# 19_WIFI_BLE.net
KiCad netlist of a schematic drawn in Altium Designer
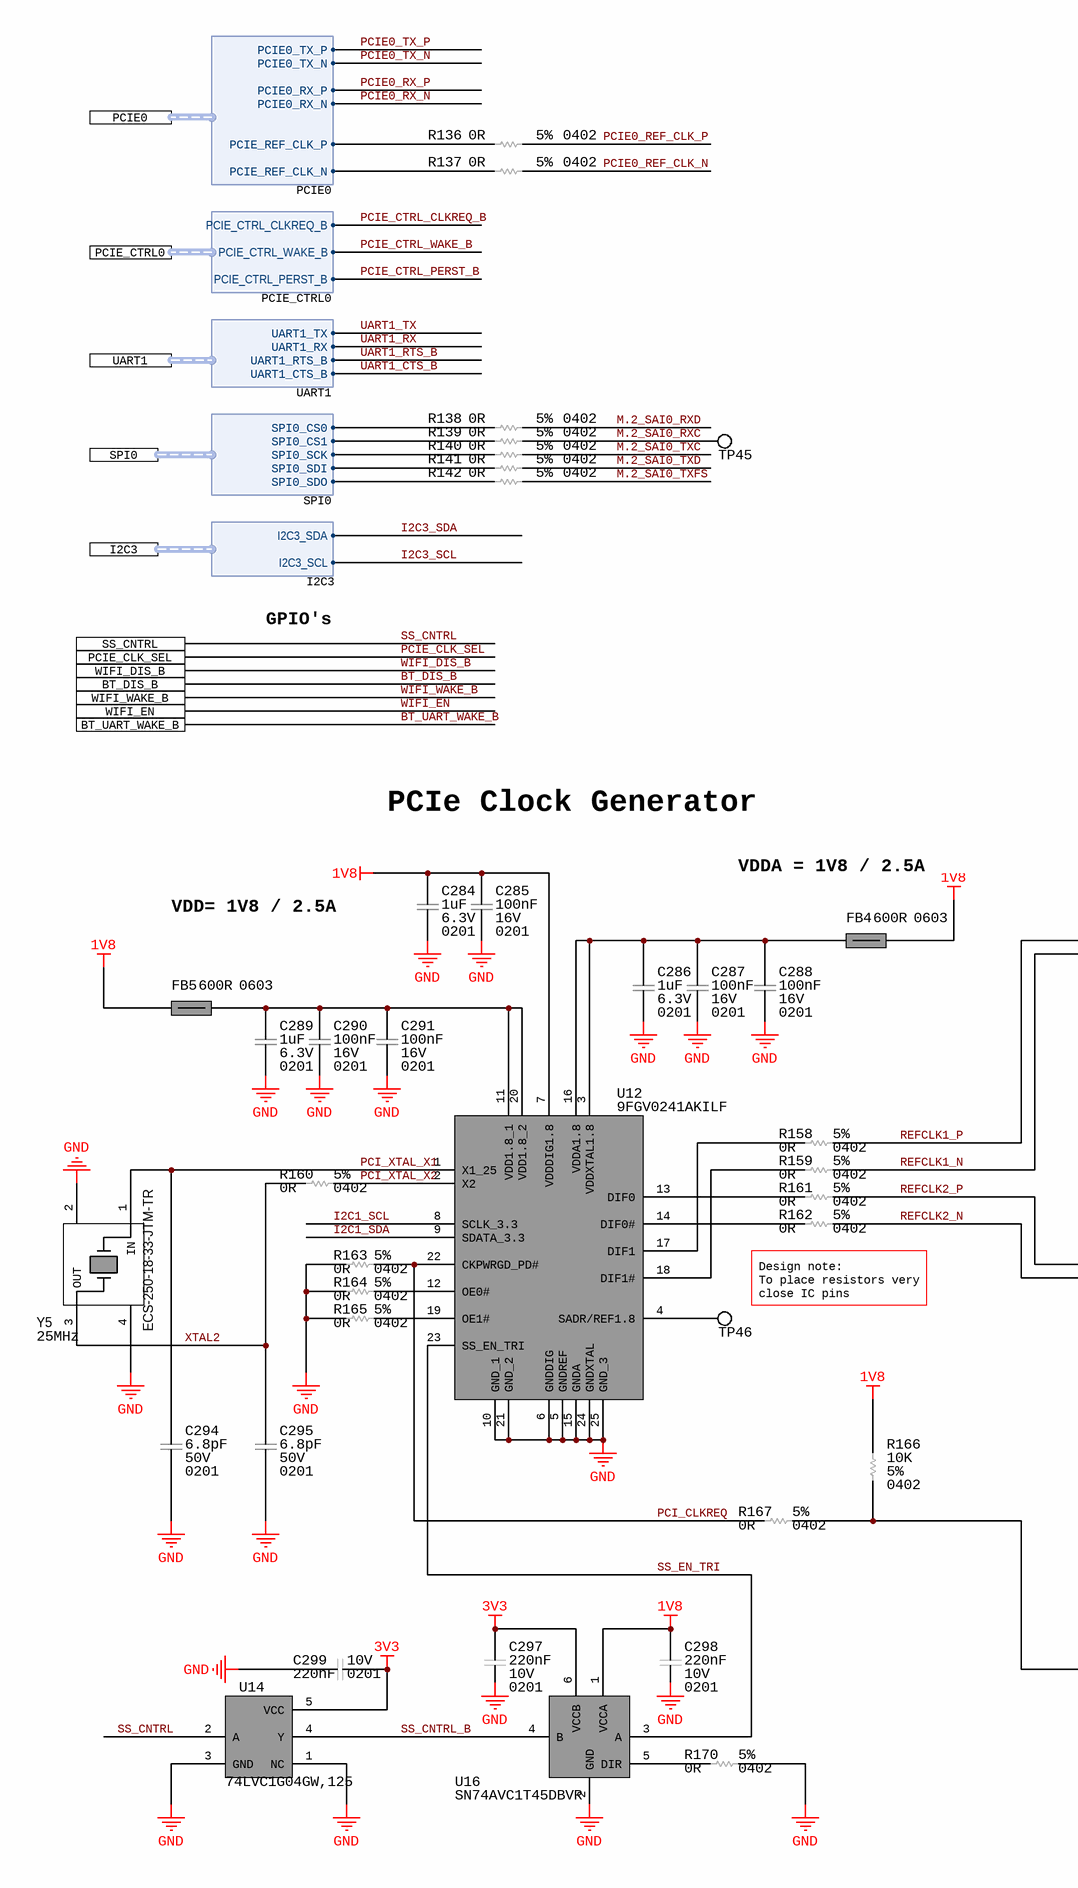
[diagram p0: 19_WIFI_BLE.SchDoc, left]
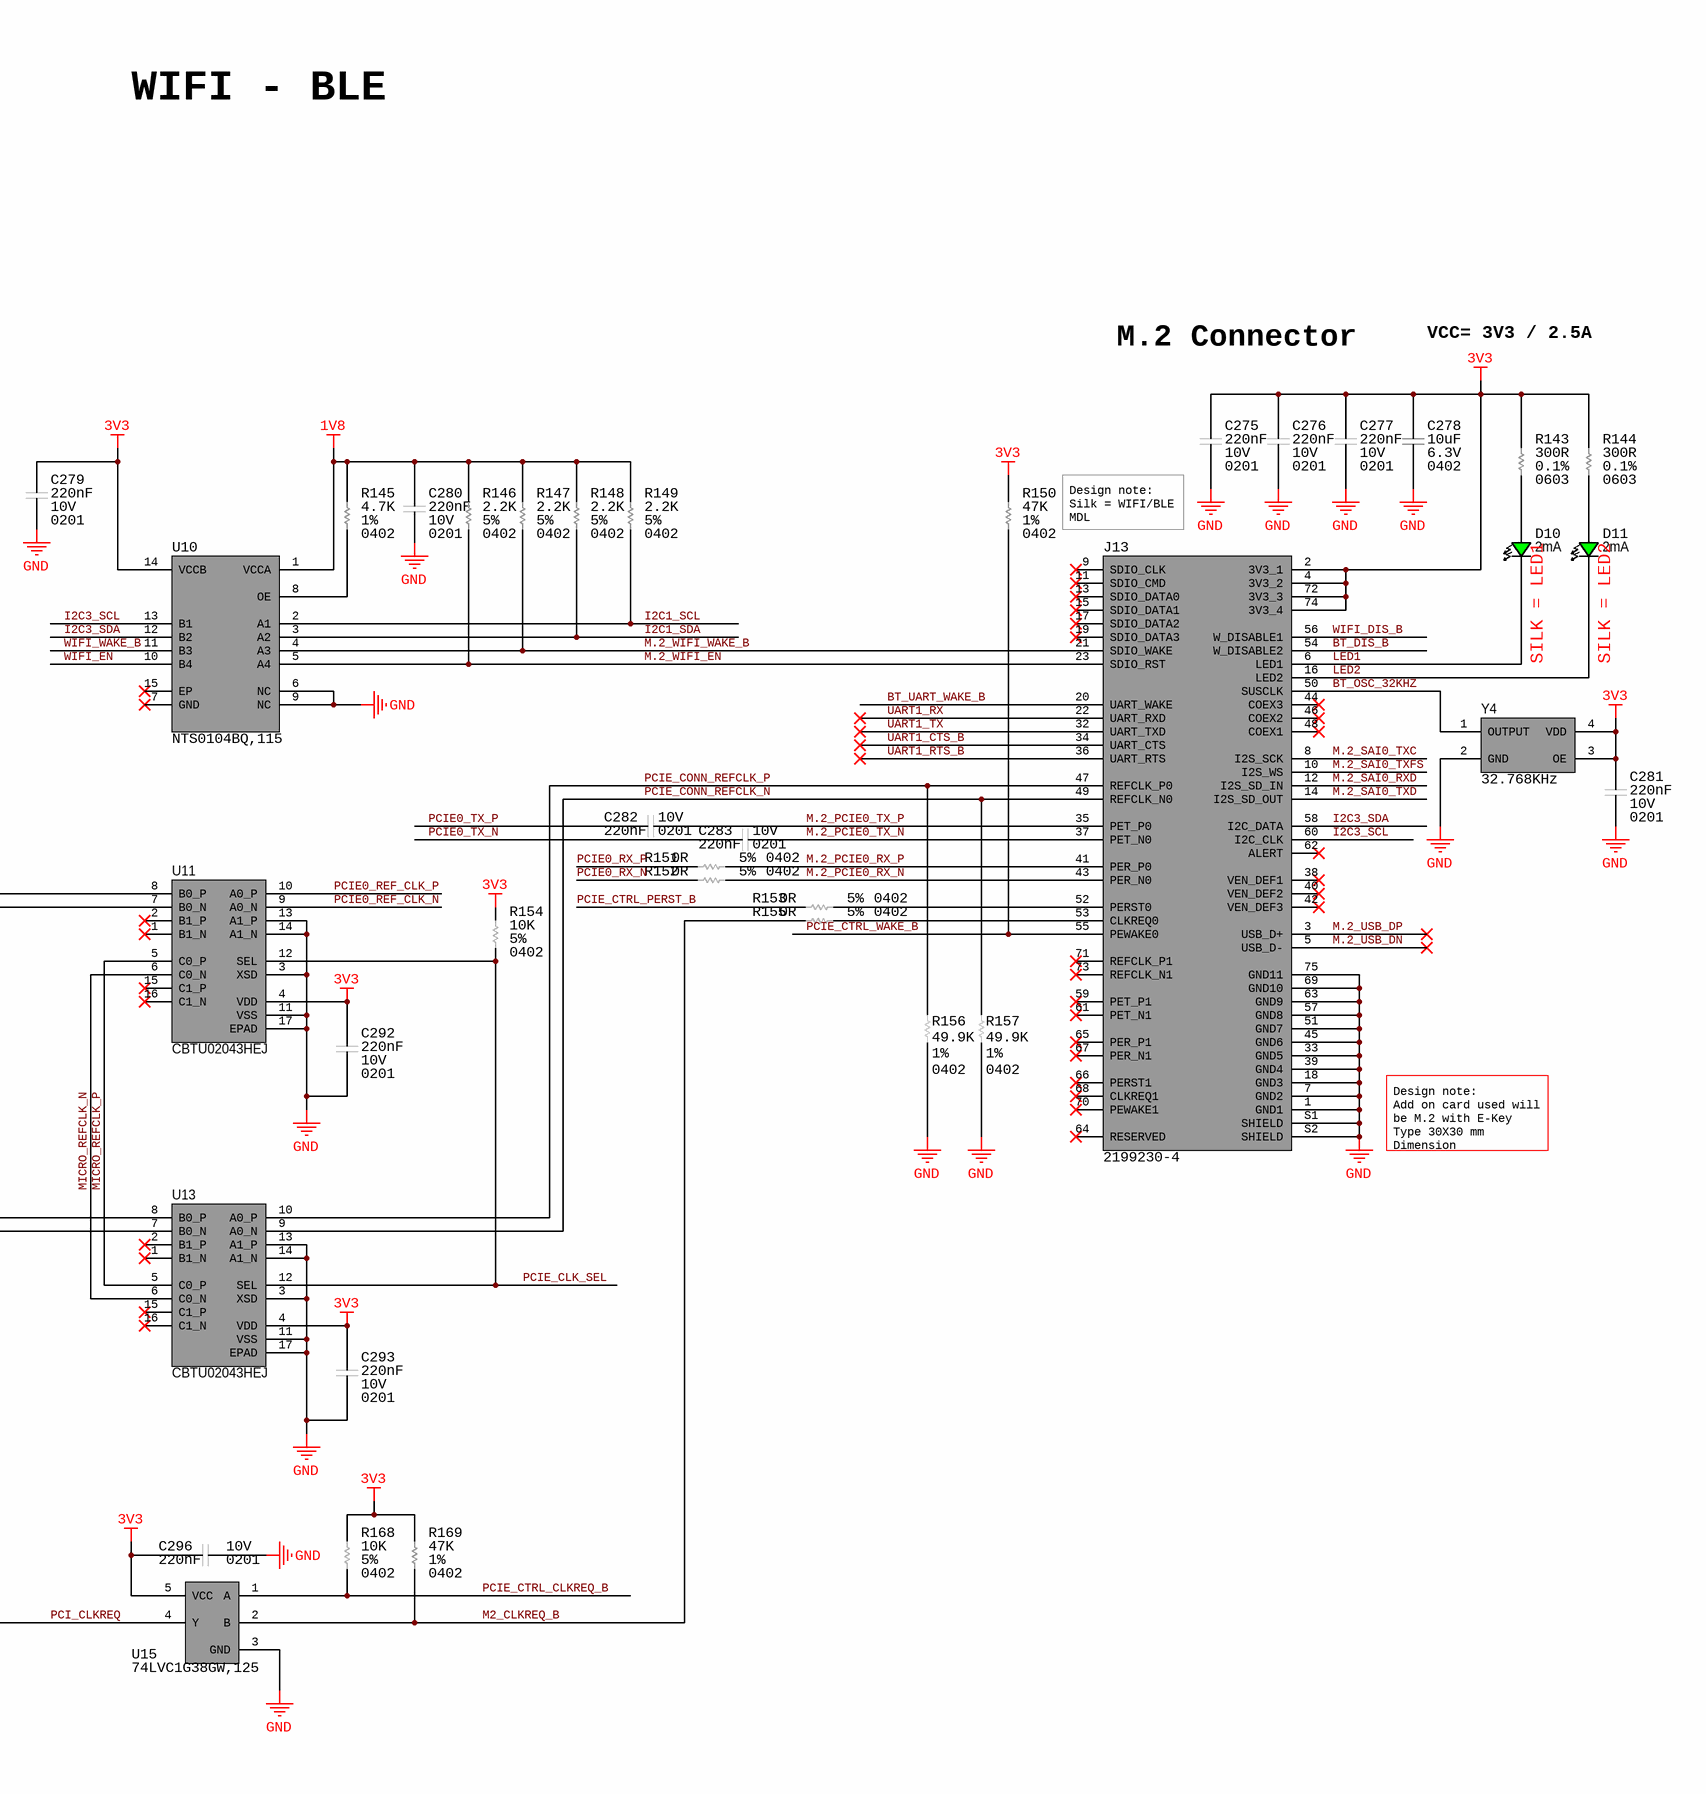
[diagram p1: 19_WIFI_BLE.SchDoc, right]

(export (version "E")
  (design (tool "Eeschema 10.0.6"))
  (components
    (comp (ref "C275")
      (value "LMK063BJ224MP-F")
      (footprint "CAP_0201_CAPC0603X03N")
      (description "Multilayer Ceramic Capacitors (High dielectric type), 10V, 0.22 uF, ± 20 %, 0201, X5R, RoHS")
      (fields
        (field (name "MANUFACTURER") "Taiyo Yuden")
        (field (name "TOLERANCE") "20%")
        (field (name "VOLTAGE RATING (DC)") "10V")
        (field (name "CAPACITANCE") "220nF")
        (field (name "CASE/PACKAGE") "0201")
      )
      (libsource (lib "Electronic Devices_LIB") (part "CAP_0.22UF_10V_X5R_0201"))
    )
    (comp (ref "C276")
      (value "LMK063BJ224MP-F")
      (footprint "CAP_0201_CAPC0603X03N")
      (description "Multilayer Ceramic Capacitors (High dielectric type), 10V, 0.22 uF, ± 20 %, 0201, X5R, RoHS")
      (fields
        (field (name "MANUFACTURER") "Taiyo Yuden")
        (field (name "TOLERANCE") "20%")
        (field (name "VOLTAGE RATING (DC)") "10V")
        (field (name "CAPACITANCE") "220nF")
        (field (name "CASE/PACKAGE") "0201")
      )
      (libsource (lib "Electronic Devices_LIB") (part "CAP_0.22UF_10V_X5R_0201"))
    )
    (comp (ref "C277")
      (value "LMK063BJ224MP-F")
      (footprint "CAP_0201_CAPC0603X03N")
      (description "Multilayer Ceramic Capacitors (High dielectric type), 10V, 0.22 uF, ± 20 %, 0201, X5R, RoHS")
      (fields
        (field (name "MANUFACTURER") "Taiyo Yuden")
        (field (name "TOLERANCE") "20%")
        (field (name "VOLTAGE RATING (DC)") "10V")
        (field (name "CAPACITANCE") "220nF")
        (field (name "CASE/PACKAGE") "0201")
      )
      (libsource (lib "Electronic Devices_LIB") (part "CAP_0.22UF_10V_X5R_0201"))
    )
    (comp (ref "C278")
      (value "CL05A106MQ5NUNC")
      (footprint "CAP_0402_CAPC1005X05N")
      (description "Cap Ceramic 10uF 6.3V X5R 20% SMD 0402 85C T/R")
      (fields
        (field (name "MANUFACTURER") "Samsung")
        (field (name "TOLERANCE") "20%")
        (field (name "CASE/PACKAGE") "0402")
        (field (name "CAPACITANCE") "10uF")
        (field (name "VOLTAGE RATING") "6.3V")
      )
      (libsource (lib "Electronic Devices_LIB") (part "CAP_10UF_6.3V_X5R_0402"))
    )
    (comp (ref "C279")
      (value "LMK063BJ224MP-F")
      (footprint "CAP_0201_CAPC0603X03N")
      (description "Multilayer Ceramic Capacitors (High dielectric type), 10V, 0.22 uF, ± 20 %, 0201, X5R, RoHS")
      (fields
        (field (name "MANUFACTURER") "Taiyo Yuden")
        (field (name "TOLERANCE") "20%")
        (field (name "VOLTAGE RATING (DC)") "10V")
        (field (name "CAPACITANCE") "220nF")
        (field (name "CASE/PACKAGE") "0201")
      )
      (libsource (lib "Electronic Devices_LIB") (part "CAP_0.22UF_10V_X5R_0201"))
    )
    (comp (ref "C280")
      (value "LMK063BJ224MP-F")
      (footprint "CAP_0201_CAPC0603X03N")
      (description "Multilayer Ceramic Capacitors (High dielectric type), 10V, 0.22 uF, ± 20 %, 0201, X5R, RoHS")
      (fields
        (field (name "MANUFACTURER") "Taiyo Yuden")
        (field (name "TOLERANCE") "20%")
        (field (name "VOLTAGE RATING (DC)") "10V")
        (field (name "CAPACITANCE") "220nF")
        (field (name "CASE/PACKAGE") "0201")
      )
      (libsource (lib "Electronic Devices_LIB") (part "CAP_0.22UF_10V_X5R_0201"))
    )
    (comp (ref "C281")
      (value "LMK063BJ224MP-F")
      (footprint "CAP_0201_CAPC0603X03N")
      (description "Multilayer Ceramic Capacitors (High dielectric type), 10V, 0.22 uF, ± 20 %, 0201, X5R, RoHS")
      (fields
        (field (name "MANUFACTURER") "Taiyo Yuden")
        (field (name "TOLERANCE") "20%")
        (field (name "VOLTAGE RATING (DC)") "10V")
        (field (name "CAPACITANCE") "220nF")
        (field (name "CASE/PACKAGE") "0201")
      )
      (libsource (lib "Electronic Devices_LIB") (part "CAP_0.22UF_10V_X5R_0201"))
    )
    (comp (ref "C282")
      (value "LMK063BJ224MP-F")
      (footprint "CAP_0201_CAPC0603X03N")
      (description "Multilayer Ceramic Capacitors (High dielectric type), 10V, 0.22 uF, ± 20 %, 0201, X5R, RoHS")
      (fields
        (field (name "MANUFACTURER") "Taiyo Yuden")
        (field (name "TOLERANCE") "20%")
        (field (name "VOLTAGE RATING (DC)") "10V")
        (field (name "CAPACITANCE") "220nF")
        (field (name "CASE/PACKAGE") "0201")
      )
      (libsource (lib "Electronic Devices_LIB") (part "CAP_0.22UF_10V_X5R_0201"))
    )
    (comp (ref "C283")
      (value "LMK063BJ224MP-F")
      (footprint "CAP_0201_CAPC0603X03N")
      (description "Multilayer Ceramic Capacitors (High dielectric type), 10V, 0.22 uF, ± 20 %, 0201, X5R, RoHS")
      (fields
        (field (name "MANUFACTURER") "Taiyo Yuden")
        (field (name "TOLERANCE") "20%")
        (field (name "VOLTAGE RATING (DC)") "10V")
        (field (name "CAPACITANCE") "220nF")
        (field (name "CASE/PACKAGE") "0201")
      )
      (libsource (lib "Electronic Devices_LIB") (part "CAP_0.22UF_10V_X5R_0201"))
    )
    (comp (ref "C284")
      (value "02016D105MAT2A")
      (footprint "CAP_0201_CAPC0603X03N")
      (description "0201 1 uF 6.3 V ±20 % Tolerance X5R Surface Mount Multilayer Ceramic Capacitor")
      (fields
        (field (name "MANUFACTURER") "Kyocera AVX")
        (field (name "TOLERANCE") "20%")
        (field (name "VOLTAGE RATING (DC)") "6.3V")
        (field (name "CAPACITANCE") "1uF")
        (field (name "CASE/PACKAGE") "0201")
      )
      (libsource (lib "Electronic Devices_LIB") (part "CAP_1UF_6.3V_X5R_0201"))
    )
    (comp (ref "C285")
      (value "GRM033C71C104KE14D")
      (footprint "CAP_0201_CAPC0603X03N")
      (description "Multilayer Ceramic Capacitor, 0.1 uF, 16 V, ± 10%, X7S, 0201 [0603 Metric]")
      (fields
        (field (name "MANUFACTURER") "Murata")
        (field (name "TOLERANCE") "10%")
        (field (name "VOLTAGE RATING") "16V")
        (field (name "CAPACITANCE") "100nF")
        (field (name "CASE/PACKAGE") "0201")
      )
      (libsource (lib "Electronic Devices_LIB") (part "CAP_100nF_16V_X7S_0201"))
    )
    (comp (ref "C286")
      (value "02016D105MAT2A")
      (footprint "CAP_0201_CAPC0603X03N")
      (description "0201 1 uF 6.3 V ±20 % Tolerance X5R Surface Mount Multilayer Ceramic Capacitor")
      (fields
        (field (name "MANUFACTURER") "Kyocera AVX")
        (field (name "TOLERANCE") "20%")
        (field (name "VOLTAGE RATING (DC)") "6.3V")
        (field (name "CAPACITANCE") "1uF")
        (field (name "CASE/PACKAGE") "0201")
      )
      (libsource (lib "Electronic Devices_LIB") (part "CAP_1UF_6.3V_X5R_0201"))
    )
    (comp (ref "C287")
      (value "GRM033C71C104KE14D")
      (footprint "CAP_0201_CAPC0603X03N")
      (description "Multilayer Ceramic Capacitor, 0.1 uF, 16 V, ± 10%, X7S, 0201 [0603 Metric]")
      (fields
        (field (name "MANUFACTURER") "Murata")
        (field (name "TOLERANCE") "10%")
        (field (name "VOLTAGE RATING") "16V")
        (field (name "CAPACITANCE") "100nF")
        (field (name "CASE/PACKAGE") "0201")
      )
      (libsource (lib "Electronic Devices_LIB") (part "CAP_100nF_16V_X7S_0201"))
    )
    (comp (ref "C288")
      (value "GRM033C71C104KE14D")
      (footprint "CAP_0201_CAPC0603X03N")
      (description "Multilayer Ceramic Capacitor, 0.1 uF, 16 V, ± 10%, X7S, 0201 [0603 Metric]")
      (fields
        (field (name "MANUFACTURER") "Murata")
        (field (name "TOLERANCE") "10%")
        (field (name "VOLTAGE RATING") "16V")
        (field (name "CAPACITANCE") "100nF")
        (field (name "CASE/PACKAGE") "0201")
      )
      (libsource (lib "Electronic Devices_LIB") (part "CAP_100nF_16V_X7S_0201"))
    )
    (comp (ref "C289")
      (value "02016D105MAT2A")
      (footprint "CAP_0201_CAPC0603X03N")
      (description "0201 1 uF 6.3 V ±20 % Tolerance X5R Surface Mount Multilayer Ceramic Capacitor")
      (fields
        (field (name "MANUFACTURER") "Kyocera AVX")
        (field (name "TOLERANCE") "20%")
        (field (name "VOLTAGE RATING (DC)") "6.3V")
        (field (name "CAPACITANCE") "1uF")
        (field (name "CASE/PACKAGE") "0201")
      )
      (libsource (lib "Electronic Devices_LIB") (part "CAP_1UF_6.3V_X5R_0201"))
    )
    (comp (ref "C290")
      (value "GRM033C71C104KE14D")
      (footprint "CAP_0201_CAPC0603X03N")
      (description "Multilayer Ceramic Capacitor, 0.1 uF, 16 V, ± 10%, X7S, 0201 [0603 Metric]")
      (fields
        (field (name "MANUFACTURER") "Murata")
        (field (name "TOLERANCE") "10%")
        (field (name "VOLTAGE RATING") "16V")
        (field (name "CAPACITANCE") "100nF")
        (field (name "CASE/PACKAGE") "0201")
      )
      (libsource (lib "Electronic Devices_LIB") (part "CAP_100nF_16V_X7S_0201"))
    )
    (comp (ref "C291")
      (value "GRM033C71C104KE14D")
      (footprint "CAP_0201_CAPC0603X03N")
      (description "Multilayer Ceramic Capacitor, 0.1 uF, 16 V, ± 10%, X7S, 0201 [0603 Metric]")
      (fields
        (field (name "MANUFACTURER") "Murata")
        (field (name "TOLERANCE") "10%")
        (field (name "VOLTAGE RATING") "16V")
        (field (name "CAPACITANCE") "100nF")
        (field (name "CASE/PACKAGE") "0201")
      )
      (libsource (lib "Electronic Devices_LIB") (part "CAP_100nF_16V_X7S_0201"))
    )
    (comp (ref "C292")
      (value "LMK063BJ224MP-F")
      (footprint "CAP_0201_CAPC0603X03N")
      (description "Multilayer Ceramic Capacitors (High dielectric type), 10V, 0.22 uF, ± 20 %, 0201, X5R, RoHS")
      (fields
        (field (name "MANUFACTURER") "Taiyo Yuden")
        (field (name "TOLERANCE") "20%")
        (field (name "VOLTAGE RATING (DC)") "10V")
        (field (name "CAPACITANCE") "220nF")
        (field (name "CASE/PACKAGE") "0201")
      )
      (libsource (lib "Electronic Devices_LIB") (part "CAP_0.22UF_10V_X5R_0201"))
    )
    (comp (ref "C293")
      (value "LMK063BJ224MP-F")
      (footprint "CAP_0201_CAPC0603X03N")
      (description "Multilayer Ceramic Capacitors (High dielectric type), 10V, 0.22 uF, ± 20 %, 0201, X5R, RoHS")
      (fields
        (field (name "MANUFACTURER") "Taiyo Yuden")
        (field (name "TOLERANCE") "20%")
        (field (name "VOLTAGE RATING (DC)") "10V")
        (field (name "CAPACITANCE") "220nF")
        (field (name "CASE/PACKAGE") "0201")
      )
      (libsource (lib "Electronic Devices_LIB") (part "CAP_0.22UF_10V_X5R_0201"))
    )
    (comp (ref "C294")
      (value "GRM0335C1H6R8BA01D")
      (footprint "CAP_0201_CAPC0603X03N")
      (description "Cap Ceramic 6.8pF 50V C0G 0.1pF Pad SMD 0201 125C T/R")
      (fields
        (field (name "MANUFACTURER") "Murata")
        (field (name "CAPACITANCE") "6.8pF")
        (field (name "VOLTAGE RATING") "50V")
        (field (name "CASE/PACKAGE") "0201")
      )
      (libsource (lib "Electronic Devices_LIB") (part "CAP_6.8pF_50V_NP0_0201"))
    )
    (comp (ref "C295")
      (value "GRM0335C1H6R8BA01D")
      (footprint "CAP_0201_CAPC0603X03N")
      (description "Cap Ceramic 6.8pF 50V C0G 0.1pF Pad SMD 0201 125C T/R")
      (fields
        (field (name "MANUFACTURER") "Murata")
        (field (name "CAPACITANCE") "6.8pF")
        (field (name "VOLTAGE RATING") "50V")
        (field (name "CASE/PACKAGE") "0201")
      )
      (libsource (lib "Electronic Devices_LIB") (part "CAP_6.8pF_50V_NP0_0201"))
    )
    (comp (ref "C296")
      (value "LMK063BJ224MP-F")
      (footprint "CAP_0201_CAPC0603X03N")
      (description "Multilayer Ceramic Capacitors (High dielectric type), 10V, 0.22 uF, ± 20 %, 0201, X5R, RoHS")
      (fields
        (field (name "MANUFACTURER") "Taiyo Yuden")
        (field (name "TOLERANCE") "20%")
        (field (name "VOLTAGE RATING (DC)") "10V")
        (field (name "CAPACITANCE") "220nF")
        (field (name "CASE/PACKAGE") "0201")
      )
      (libsource (lib "Electronic Devices_LIB") (part "CAP_0.22UF_10V_X5R_0201"))
    )
    (comp (ref "C297")
      (value "LMK063BJ224MP-F")
      (footprint "CAP_0201_CAPC0603X03N")
      (description "Multilayer Ceramic Capacitors (High dielectric type), 10V, 0.22 uF, ± 20 %, 0201, X5R, RoHS")
      (fields
        (field (name "MANUFACTURER") "Taiyo Yuden")
        (field (name "TOLERANCE") "20%")
        (field (name "VOLTAGE RATING (DC)") "10V")
        (field (name "CAPACITANCE") "220nF")
        (field (name "CASE/PACKAGE") "0201")
      )
      (libsource (lib "Electronic Devices_LIB") (part "CAP_0.22UF_10V_X5R_0201"))
    )
    (comp (ref "C298")
      (value "LMK063BJ224MP-F")
      (footprint "CAP_0201_CAPC0603X03N")
      (description "Multilayer Ceramic Capacitors (High dielectric type), 10V, 0.22 uF, ± 20 %, 0201, X5R, RoHS")
      (fields
        (field (name "MANUFACTURER") "Taiyo Yuden")
        (field (name "TOLERANCE") "20%")
        (field (name "VOLTAGE RATING (DC)") "10V")
        (field (name "CAPACITANCE") "220nF")
        (field (name "CASE/PACKAGE") "0201")
      )
      (libsource (lib "Electronic Devices_LIB") (part "CAP_0.22UF_10V_X5R_0201"))
    )
    (comp (ref "C299")
      (value "LMK063BJ224MP-F")
      (footprint "CAP_0201_CAPC0603X03N")
      (description "Multilayer Ceramic Capacitors (High dielectric type), 10V, 0.22 uF, ± 20 %, 0201, X5R, RoHS")
      (fields
        (field (name "MANUFACTURER") "Taiyo Yuden")
        (field (name "TOLERANCE") "20%")
        (field (name "VOLTAGE RATING (DC)") "10V")
        (field (name "CAPACITANCE") "220nF")
        (field (name "CASE/PACKAGE") "0201")
      )
      (libsource (lib "Electronic Devices_LIB") (part "CAP_0.22UF_10V_X5R_0201"))
    )
    (comp (ref "D10")
      (value "APDA3020LZGCK")
      (footprint "LED_GREEN_APDA3020LZGCK")
      (description "LED GREEN CLEAR 2SMD R/A  1500mcd")
      (fields (field (name "MANUFACTURER") "Kingbright") (field (name "TEST CURRENT") "2mA"))
      (libsource (lib "Electronic Devices_LIB") (part "LED_DIO_GREEN_2mA_APDA3020LZGCK"))
    )
    (comp (ref "D11")
      (value "APDA3020LZGCK")
      (footprint "LED_GREEN_APDA3020LZGCK")
      (description "LED GREEN CLEAR 2SMD R/A  1500mcd")
      (fields (field (name "MANUFACTURER") "Kingbright") (field (name "TEST CURRENT") "2mA"))
      (libsource (lib "Electronic Devices_LIB") (part "LED_DIO_GREEN_2mA_APDA3020LZGCK"))
    )
    (comp (ref "FB4")
      (value "742792653")
      (footprint "IND_0603_INDC1608X08N")
      (description "Chip NTC Thermistors (Sensor), Resistance (at 25°C)=10kΩ, Resistance Tolerance (at 25°C)=±1%")
      (fields
        (field (name "MANUFACTURER") "Wurth Electronics")
        (field (name "TOLERANCE") "25%")
        (field (name "IMPEDANCE") "600R")
        (field (name "CASE CODE (IMPERIAL)") "0603")
      )
      (libsource (lib "Electronic Devices_LIB") (part "IND_FERRITE_BEADS_600R_300mA_0603_742792653"))
    )
    (comp (ref "FB5")
      (value "742792653")
      (footprint "IND_0603_INDC1608X08N")
      (description "Chip NTC Thermistors (Sensor), Resistance (at 25°C)=10kΩ, Resistance Tolerance (at 25°C)=±1%")
      (fields
        (field (name "MANUFACTURER") "Wurth Electronics")
        (field (name "TOLERANCE") "25%")
        (field (name "IMPEDANCE") "600R")
        (field (name "CASE CODE (IMPERIAL)") "0603")
      )
      (libsource (lib "Electronic Devices_LIB") (part "IND_FERRITE_BEADS_600R_300mA_0603_742792653"))
    )
    (comp (ref "J13")
      (value "2199230-4")
      (footprint "TE_21992304")
      (description "CONNECTOR, BACKPLANE, HOUSING, RCPT, 67POS, 2ROW; Connector Type: Card Edge; Seri")
      (fields (field (name "MANUFACTURER") "TE Connectivity"))
      (libsource (lib "Electronic Devices_LIB") (part "CONN_M.2_FEMALE_2199230-4"))
    )
    (comp (ref "R136")
      (value "ERJ-2GE0R00X")
      (footprint "RES_0402_RESC1005X04N")
      (description "SMD Chip Resistor, Jumper, 0 ohm, 100 mW, 0402 [1005 Metric], Thick Film, General Purpose")
      (fields
        (field (name "MANUFACTURER") "Panasonic")
        (field (name "CASE CODE (IMPERIAL)") "0402")
        (field (name "TOLERANCE") "5%")
        (field (name "RESISTANCE") "0R")
      )
      (libsource (lib "Electronic Devices_LIB") (part "RES_0R_5%_100mW_0402"))
    )
    (comp (ref "R137")
      (value "ERJ-2GE0R00X")
      (footprint "RES_0402_RESC1005X04N")
      (description "SMD Chip Resistor, Jumper, 0 ohm, 100 mW, 0402 [1005 Metric], Thick Film, General Purpose")
      (fields
        (field (name "MANUFACTURER") "Panasonic")
        (field (name "CASE CODE (IMPERIAL)") "0402")
        (field (name "TOLERANCE") "5%")
        (field (name "RESISTANCE") "0R")
      )
      (libsource (lib "Electronic Devices_LIB") (part "RES_0R_5%_100mW_0402"))
    )
    (comp (ref "R138")
      (value "ERJ-2GE0R00X")
      (footprint "RES_0402_RESC1005X04N")
      (description "SMD Chip Resistor, Jumper, 0 ohm, 100 mW, 0402 [1005 Metric], Thick Film, General Purpose")
      (fields
        (field (name "MANUFACTURER") "Panasonic")
        (field (name "CASE CODE (IMPERIAL)") "0402")
        (field (name "TOLERANCE") "5%")
        (field (name "RESISTANCE") "0R")
      )
      (libsource (lib "Electronic Devices_LIB") (part "RES_0R_5%_100mW_0402"))
    )
    (comp (ref "R139")
      (value "ERJ-2GE0R00X")
      (footprint "RES_0402_RESC1005X04N")
      (description "SMD Chip Resistor, Jumper, 0 ohm, 100 mW, 0402 [1005 Metric], Thick Film, General Purpose")
      (fields
        (field (name "MANUFACTURER") "Panasonic")
        (field (name "CASE CODE (IMPERIAL)") "0402")
        (field (name "TOLERANCE") "5%")
        (field (name "RESISTANCE") "0R")
      )
      (libsource (lib "Electronic Devices_LIB") (part "RES_0R_5%_100mW_0402"))
    )
    (comp (ref "R140")
      (value "ERJ-2GE0R00X")
      (footprint "RES_0402_RESC1005X04N")
      (description "SMD Chip Resistor, Jumper, 0 ohm, 100 mW, 0402 [1005 Metric], Thick Film, General Purpose")
      (fields
        (field (name "MANUFACTURER") "Panasonic")
        (field (name "CASE CODE (IMPERIAL)") "0402")
        (field (name "TOLERANCE") "5%")
        (field (name "RESISTANCE") "0R")
      )
      (libsource (lib "Electronic Devices_LIB") (part "RES_0R_5%_100mW_0402"))
    )
    (comp (ref "R141")
      (value "ERJ-2GE0R00X")
      (footprint "RES_0402_RESC1005X04N")
      (description "SMD Chip Resistor, Jumper, 0 ohm, 100 mW, 0402 [1005 Metric], Thick Film, General Purpose")
      (fields
        (field (name "MANUFACTURER") "Panasonic")
        (field (name "CASE CODE (IMPERIAL)") "0402")
        (field (name "TOLERANCE") "5%")
        (field (name "RESISTANCE") "0R")
      )
      (libsource (lib "Electronic Devices_LIB") (part "RES_0R_5%_100mW_0402"))
    )
    (comp (ref "R142")
      (value "ERJ-2GE0R00X")
      (footprint "RES_0402_RESC1005X04N")
      (description "SMD Chip Resistor, Jumper, 0 ohm, 100 mW, 0402 [1005 Metric], Thick Film, General Purpose")
      (fields
        (field (name "MANUFACTURER") "Panasonic")
        (field (name "CASE CODE (IMPERIAL)") "0402")
        (field (name "TOLERANCE") "5%")
        (field (name "RESISTANCE") "0R")
      )
      (libsource (lib "Electronic Devices_LIB") (part "RES_0R_5%_100mW_0402"))
    )
    (comp (ref "R143")
      (value "RT0603BRD07300RL")
      (footprint "RES_0603_RESC1608X04N")
      (description "Res Thin Film 0603 300 Ohm 0.1% 0.1W(1/10W) ±25ppm/C Pad SMD T/R")
      (fields
        (field (name "MANUFACTURER") "Yageo")
        (field (name "CASE CODE (IMPERIAL)") "0603")
        (field (name "TOLERANCE") "0.1%")
        (field (name "RESISTANCE") "300R")
      )
      (libsource (lib "Electronic Devices_LIB") (part "RES_300R_0.1%_100mW_0603"))
    )
    (comp (ref "R144")
      (value "RT0603BRD07300RL")
      (footprint "RES_0603_RESC1608X04N")
      (description "Res Thin Film 0603 300 Ohm 0.1% 0.1W(1/10W) ±25ppm/C Pad SMD T/R")
      (fields
        (field (name "MANUFACTURER") "Yageo")
        (field (name "CASE CODE (IMPERIAL)") "0603")
        (field (name "TOLERANCE") "0.1%")
        (field (name "RESISTANCE") "300R")
      )
      (libsource (lib "Electronic Devices_LIB") (part "RES_300R_0.1%_100mW_0603"))
    )
    (comp (ref "R145")
      (value "ERJ-2RKF4701X")
      (footprint "RES_0402_RESC1005X04N")
      (description "Res Thick Film 0402 4.7K Ohm 1% 0.1W ±100ppm/°C Molded SMD Punched Carrier T/R")
      (fields
        (field (name "MANUFACTURER") "Panasonic")
        (field (name "TOLERANCE") "1%")
        (field (name "CASE CODE (IMPERIAL)") "0402")
        (field (name "RESISTANCE") "4.7K")
      )
      (libsource (lib "Electronic Devices_LIB") (part "RES_4.7K_1%_100mW_0402"))
    )
    (comp (ref "R146")
      (value "RC0402JR-072K2L")
      (footprint "RES_0402_RESC1005X04N")
      (description "SMD Chip Resistor, 2.2 kOhm, ± 5%, 63 mW, 0402 [1005 Metric], Thick Film, General Purpose")
      (fields
        (field (name "MANUFACTURER") "Yageo")
        (field (name "TOLERANCE") "5%")
        (field (name "RESISTANCE") "2.2K")
        (field (name "CASE/PACKAGE") "0402")
      )
      (libsource (lib "Electronic Devices_LIB") (part "RES_2.2K_5%_63mW_0402"))
    )
    (comp (ref "R147")
      (value "RC0402JR-072K2L")
      (footprint "RES_0402_RESC1005X04N")
      (description "SMD Chip Resistor, 2.2 kOhm, ± 5%, 63 mW, 0402 [1005 Metric], Thick Film, General Purpose")
      (fields
        (field (name "MANUFACTURER") "Yageo")
        (field (name "TOLERANCE") "5%")
        (field (name "RESISTANCE") "2.2K")
        (field (name "CASE/PACKAGE") "0402")
      )
      (libsource (lib "Electronic Devices_LIB") (part "RES_2.2K_5%_63mW_0402"))
    )
    (comp (ref "R148")
      (value "RC0402JR-072K2L")
      (footprint "RES_0402_RESC1005X04N")
      (description "SMD Chip Resistor, 2.2 kOhm, ± 5%, 63 mW, 0402 [1005 Metric], Thick Film, General Purpose")
      (fields
        (field (name "MANUFACTURER") "Yageo")
        (field (name "TOLERANCE") "5%")
        (field (name "RESISTANCE") "2.2K")
        (field (name "CASE/PACKAGE") "0402")
      )
      (libsource (lib "Electronic Devices_LIB") (part "RES_2.2K_5%_63mW_0402"))
    )
    (comp (ref "R149")
      (value "RC0402JR-072K2L")
      (footprint "RES_0402_RESC1005X04N")
      (description "SMD Chip Resistor, 2.2 kOhm, ± 5%, 63 mW, 0402 [1005 Metric], Thick Film, General Purpose")
      (fields
        (field (name "MANUFACTURER") "Yageo")
        (field (name "TOLERANCE") "5%")
        (field (name "RESISTANCE") "2.2K")
        (field (name "CASE/PACKAGE") "0402")
      )
      (libsource (lib "Electronic Devices_LIB") (part "RES_2.2K_5%_63mW_0402"))
    )
    (comp (ref "R150")
      (value "ERJ-2RKF4702X")
      (footprint "RES_0402_RESC1005X04N")
      (description "Res Thick Film 0402 47K Ohm 1% 0.1W ±100ppm/°C Molded SMD Punched Carrier T/R")
      (fields
        (field (name "MANUFACTURER") "Panasonic")
        (field (name "TOLERANCE") "1%")
        (field (name "RESISTANCE") "47K")
        (field (name "CASE/PACKAGE") "0402")
      )
      (libsource (lib "Electronic Devices_LIB") (part "RES_47K_1%_100MW_0402"))
    )
    (comp (ref "R151")
      (value "ERJ-2GE0R00X")
      (footprint "RES_0402_RESC1005X04N")
      (description "SMD Chip Resistor, Jumper, 0 ohm, 100 mW, 0402 [1005 Metric], Thick Film, General Purpose")
      (fields
        (field (name "MANUFACTURER") "Panasonic")
        (field (name "CASE CODE (IMPERIAL)") "0402")
        (field (name "TOLERANCE") "5%")
        (field (name "RESISTANCE") "0R")
      )
      (libsource (lib "Electronic Devices_LIB") (part "RES_0R_5%_100mW_0402"))
    )
    (comp (ref "R152")
      (value "ERJ-2GE0R00X")
      (footprint "RES_0402_RESC1005X04N")
      (description "SMD Chip Resistor, Jumper, 0 ohm, 100 mW, 0402 [1005 Metric], Thick Film, General Purpose")
      (fields
        (field (name "MANUFACTURER") "Panasonic")
        (field (name "CASE CODE (IMPERIAL)") "0402")
        (field (name "TOLERANCE") "5%")
        (field (name "RESISTANCE") "0R")
      )
      (libsource (lib "Electronic Devices_LIB") (part "RES_0R_5%_100mW_0402"))
    )
    (comp (ref "R153")
      (value "ERJ-2GE0R00X")
      (footprint "RES_0402_RESC1005X04N")
      (description "SMD Chip Resistor, Jumper, 0 ohm, 100 mW, 0402 [1005 Metric], Thick Film, General Purpose")
      (fields
        (field (name "MANUFACTURER") "Panasonic")
        (field (name "CASE CODE (IMPERIAL)") "0402")
        (field (name "TOLERANCE") "5%")
        (field (name "RESISTANCE") "0R")
      )
      (libsource (lib "Electronic Devices_LIB") (part "RES_0R_5%_100mW_0402"))
    )
    (comp (ref "R154")
      (value "ERJ-2GEJ103X")
      (footprint "RES_0402_RESC1005X04N")
      (description "Res Thick Film 0402 10K Ohm 5% 1/10W ±200ppm/°C Molded SMD Punched Carrier T/R")
      (fields
        (field (name "MANUFACTURER") "Panasonic")
        (field (name "TOLERANCE") "5%")
        (field (name "RESISTANCE") "10K")
        (field (name "CASE/PACKAGE") "0402")
      )
      (libsource (lib "Electronic Devices_LIB") (part "RES_10K_5%_100mW_0402"))
    )
    (comp (ref "R155")
      (value "ERJ-2GE0R00X")
      (footprint "RES_0402_RESC1005X04N")
      (description "SMD Chip Resistor, Jumper, 0 ohm, 100 mW, 0402 [1005 Metric], Thick Film, General Purpose")
      (fields
        (field (name "MANUFACTURER") "Panasonic")
        (field (name "CASE CODE (IMPERIAL)") "0402")
        (field (name "TOLERANCE") "5%")
        (field (name "RESISTANCE") "0R")
      )
      (libsource (lib "Electronic Devices_LIB") (part "RES_0R_5%_100mW_0402"))
    )
    (comp (ref "R156")
      (value "CRCW040249K9FKED")
      (footprint "RES_0402_RESC1005X04N")
      (description "Res Thick Film 0402 49.9K Ohm 1% 1/16W ±100ppm/°C Molded SMD SMD Paper T/R")
      (fields
        (field (name "MANUFACTURER") "Vishay")
        (field (name "RESISTANCE") "49.9K")
        (field (name "TOLERANCE") "1%")
        (field (name "CASE/PACKAGE") "0402")
      )
      (libsource (lib "Electronic Devices_LIB") (part "RES_49.9K_1%_0.0625W_0402"))
    )
    (comp (ref "R157")
      (value "CRCW040249K9FKED")
      (footprint "RES_0402_RESC1005X04N")
      (description "Res Thick Film 0402 49.9K Ohm 1% 1/16W ±100ppm/°C Molded SMD SMD Paper T/R")
      (fields
        (field (name "MANUFACTURER") "Vishay")
        (field (name "RESISTANCE") "49.9K")
        (field (name "TOLERANCE") "1%")
        (field (name "CASE/PACKAGE") "0402")
      )
      (libsource (lib "Electronic Devices_LIB") (part "RES_49.9K_1%_0.0625W_0402"))
    )
    (comp (ref "R158")
      (value "ERJ-2GE0R00X")
      (footprint "RES_0402_RESC1005X04N")
      (description "SMD Chip Resistor, Jumper, 0 ohm, 100 mW, 0402 [1005 Metric], Thick Film, General Purpose")
      (fields
        (field (name "MANUFACTURER") "Panasonic")
        (field (name "CASE CODE (IMPERIAL)") "0402")
        (field (name "TOLERANCE") "5%")
        (field (name "RESISTANCE") "0R")
      )
      (libsource (lib "Electronic Devices_LIB") (part "RES_0R_5%_100mW_0402"))
    )
    (comp (ref "R159")
      (value "ERJ-2GE0R00X")
      (footprint "RES_0402_RESC1005X04N")
      (description "SMD Chip Resistor, Jumper, 0 ohm, 100 mW, 0402 [1005 Metric], Thick Film, General Purpose")
      (fields
        (field (name "MANUFACTURER") "Panasonic")
        (field (name "CASE CODE (IMPERIAL)") "0402")
        (field (name "TOLERANCE") "5%")
        (field (name "RESISTANCE") "0R")
      )
      (libsource (lib "Electronic Devices_LIB") (part "RES_0R_5%_100mW_0402"))
    )
    (comp (ref "R160")
      (value "ERJ-2GE0R00X")
      (footprint "RES_0402_RESC1005X04N")
      (description "SMD Chip Resistor, Jumper, 0 ohm, 100 mW, 0402 [1005 Metric], Thick Film, General Purpose")
      (fields
        (field (name "MANUFACTURER") "Panasonic")
        (field (name "CASE CODE (IMPERIAL)") "0402")
        (field (name "TOLERANCE") "5%")
        (field (name "RESISTANCE") "0R")
      )
      (libsource (lib "Electronic Devices_LIB") (part "RES_0R_5%_100mW_0402"))
    )
    (comp (ref "R161")
      (value "ERJ-2GE0R00X")
      (footprint "RES_0402_RESC1005X04N")
      (description "SMD Chip Resistor, Jumper, 0 ohm, 100 mW, 0402 [1005 Metric], Thick Film, General Purpose")
      (fields
        (field (name "MANUFACTURER") "Panasonic")
        (field (name "CASE CODE (IMPERIAL)") "0402")
        (field (name "TOLERANCE") "5%")
        (field (name "RESISTANCE") "0R")
      )
      (libsource (lib "Electronic Devices_LIB") (part "RES_0R_5%_100mW_0402"))
    )
    (comp (ref "R162")
      (value "ERJ-2GE0R00X")
      (footprint "RES_0402_RESC1005X04N")
      (description "SMD Chip Resistor, Jumper, 0 ohm, 100 mW, 0402 [1005 Metric], Thick Film, General Purpose")
      (fields
        (field (name "MANUFACTURER") "Panasonic")
        (field (name "CASE CODE (IMPERIAL)") "0402")
        (field (name "TOLERANCE") "5%")
        (field (name "RESISTANCE") "0R")
      )
      (libsource (lib "Electronic Devices_LIB") (part "RES_0R_5%_100mW_0402"))
    )
    (comp (ref "R163")
      (value "ERJ-2GE0R00X")
      (footprint "RES_0402_RESC1005X04N")
      (description "SMD Chip Resistor, Jumper, 0 ohm, 100 mW, 0402 [1005 Metric], Thick Film, General Purpose")
      (fields
        (field (name "MANUFACTURER") "Panasonic")
        (field (name "CASE CODE (IMPERIAL)") "0402")
        (field (name "TOLERANCE") "5%")
        (field (name "RESISTANCE") "0R")
      )
      (libsource (lib "Electronic Devices_LIB") (part "RES_0R_5%_100mW_0402"))
    )
    (comp (ref "R164")
      (value "ERJ-2GE0R00X")
      (footprint "RES_0402_RESC1005X04N")
      (description "SMD Chip Resistor, Jumper, 0 ohm, 100 mW, 0402 [1005 Metric], Thick Film, General Purpose")
      (fields
        (field (name "MANUFACTURER") "Panasonic")
        (field (name "CASE CODE (IMPERIAL)") "0402")
        (field (name "TOLERANCE") "5%")
        (field (name "RESISTANCE") "0R")
      )
      (libsource (lib "Electronic Devices_LIB") (part "RES_0R_5%_100mW_0402"))
    )
    (comp (ref "R165")
      (value "ERJ-2GE0R00X")
      (footprint "RES_0402_RESC1005X04N")
      (description "SMD Chip Resistor, Jumper, 0 ohm, 100 mW, 0402 [1005 Metric], Thick Film, General Purpose")
      (fields
        (field (name "MANUFACTURER") "Panasonic")
        (field (name "CASE CODE (IMPERIAL)") "0402")
        (field (name "TOLERANCE") "5%")
        (field (name "RESISTANCE") "0R")
      )
      (libsource (lib "Electronic Devices_LIB") (part "RES_0R_5%_100mW_0402"))
    )
    (comp (ref "R166")
      (value "ERJ-2GEJ103X")
      (footprint "RES_0402_RESC1005X04N")
      (description "Res Thick Film 0402 10K Ohm 5% 1/10W ±200ppm/°C Molded SMD Punched Carrier T/R")
      (fields
        (field (name "MANUFACTURER") "Panasonic")
        (field (name "TOLERANCE") "5%")
        (field (name "RESISTANCE") "10K")
        (field (name "CASE/PACKAGE") "0402")
      )
      (libsource (lib "Electronic Devices_LIB") (part "RES_10K_5%_100mW_0402"))
    )
    (comp (ref "R167")
      (value "ERJ-2GE0R00X")
      (footprint "RES_0402_RESC1005X04N")
      (description "SMD Chip Resistor, Jumper, 0 ohm, 100 mW, 0402 [1005 Metric], Thick Film, General Purpose")
      (fields
        (field (name "MANUFACTURER") "Panasonic")
        (field (name "CASE CODE (IMPERIAL)") "0402")
        (field (name "TOLERANCE") "5%")
        (field (name "RESISTANCE") "0R")
      )
      (libsource (lib "Electronic Devices_LIB") (part "RES_0R_5%_100mW_0402"))
    )
    (comp (ref "R168")
      (value "ERJ-2GEJ103X")
      (footprint "RES_0402_RESC1005X04N")
      (description "Res Thick Film 0402 10K Ohm 5% 1/10W ±200ppm/°C Molded SMD Punched Carrier T/R")
      (fields
        (field (name "MANUFACTURER") "Panasonic")
        (field (name "TOLERANCE") "5%")
        (field (name "RESISTANCE") "10K")
        (field (name "CASE/PACKAGE") "0402")
      )
      (libsource (lib "Electronic Devices_LIB") (part "RES_10K_5%_100mW_0402"))
    )
    (comp (ref "R169")
      (value "ERJ-2RKF4702X")
      (footprint "RES_0402_RESC1005X04N")
      (description "Res Thick Film 0402 47K Ohm 1% 0.1W ±100ppm/°C Molded SMD Punched Carrier T/R")
      (fields
        (field (name "MANUFACTURER") "Panasonic")
        (field (name "TOLERANCE") "1%")
        (field (name "RESISTANCE") "47K")
        (field (name "CASE/PACKAGE") "0402")
      )
      (libsource (lib "Electronic Devices_LIB") (part "RES_47K_1%_100MW_0402"))
    )
    (comp (ref "R170")
      (value "ERJ-2GE0R00X")
      (footprint "RES_0402_RESC1005X04N")
      (description "SMD Chip Resistor, Jumper, 0 ohm, 100 mW, 0402 [1005 Metric], Thick Film, General Purpose")
      (fields
        (field (name "MANUFACTURER") "Panasonic")
        (field (name "CASE CODE (IMPERIAL)") "0402")
        (field (name "TOLERANCE") "5%")
        (field (name "RESISTANCE") "0R")
      )
      (libsource (lib "Electronic Devices_LIB") (part "RES_0R_5%_100mW_0402"))
    )
    (comp (ref "TP45")
      (value "NO COMPONENT")
      (footprint "TP_PAD_0.5MM_SMD_ROUND")
      (description "Test Point, SMD pad, round, 1.5mm, 1.6mm, 3mm diameter")
      (libsource (lib "Electronic Devices_LIB") (part "TP_PAD_SMD_SMALL"))
    )
    (comp (ref "TP46")
      (value "NO COMPONENT")
      (footprint "TP_PAD_0.5MM_SMD_ROUND")
      (description "Test Point, SMD pad, round, 1.5mm, 1.6mm, 3mm diameter")
      (libsource (lib "Electronic Devices_LIB") (part "TP_PAD_SMD_SMALL"))
    )
    (comp (ref "U10")
      (value "NTS0104BQ,115")
      (footprint "QFN50P300X250X100-15N")
      (description "Voltage Level Translator Bidirectional 1 Circuit 4 Channel 50Mbps 14-DHVQFN (2.5x3)")
      (fields (field (name "MANUFACTURER") "NXP Semiconductors"))
      (libsource (lib "Electronic Devices_LIB") (part "IC_LEVEL_TRASLATE_4CH_NTS0104BQ,115"))
    )
    (comp (ref "U11")
      (value "CBTU02043HEJ")
      (footprint "IC_SW_TYPEC_CBTU02044HEJ")
      (description "USB 3.1 Gen 1 Type C switch / TAPE + REEL REEL 13\" Q1 NDP RoHS Compliant: Yes")
      (fields (field (name "MANUFACTURER") "NXP Semiconductors"))
      (libsource (lib "Electronic Devices_LIB") (part "IC_SWITCH_TYPEC_CBTU02043HEJ"))
    )
    (comp (ref "U12")
      (value "9FGV0241AKILF")
      (footprint "QFN50P400X400X100-25N-D")
      (description "Dual Output 1.8 V Very Low Power PCIE GEN1/2/3 Clock Generator - VFQFPN-24")
      (fields (field (name "MANUFACTURER") "Renesas"))
      (libsource (lib "Electronic Devices_LIB") (part "IC_CLOCK_PCIE_100MHZ_9FGV0241AKILF"))
    )
    (comp (ref "U13")
      (value "CBTU02043HEJ")
      (footprint "IC_SW_TYPEC_CBTU02044HEJ")
      (description "USB 3.1 Gen 1 Type C switch / TAPE + REEL REEL 13\" Q1 NDP RoHS Compliant: Yes")
      (fields (field (name "MANUFACTURER") "NXP Semiconductors"))
      (libsource (lib "Electronic Devices_LIB") (part "IC_SWITCH_TYPEC_CBTU02043HEJ"))
    )
    (comp (ref "U14")
      (value "74LVC1G04GW,125")
      (footprint "SOT65P210X110-5N")
      (description "74LVC Series 5.5 V Surface Mount Single Inverting Buffer - TSSOP-5")
      (fields (field (name "MANUFACTURER") "Nexperia"))
      (libsource (lib "Electronic Devices_LIB") (part "IC_INVERTER_1CH_74LVC1G04GW,125"))
    )
    (comp (ref "U15")
      (value "74LVC1G38GW,125")
      (footprint "SOT65P212X110-5N")
      (description "IC GATE NAND 1CH 2-INP 5-TSSOP")
      (fields (field (name "MANUFACTURER") "Nexperia"))
      (libsource (lib "Electronic Devices_LIB") (part "IC_GATE_NAND_1CH_74LVC1G38GW,125"))
    )
    (comp (ref "U16")
      (value "SN74AVC1T45DBVR")
      (footprint "SOT95P280X145-6N")
      (description "1.2V~3.6V 1 1 1.2V~3.6V 500Mbps SOT-23-6 Translators / Level Shifters ROHS")
      (fields (field (name "MANUFACTURER") "Texas Instruments"))
      (libsource (lib "Electronic Devices_LIB") (part "IC_LEVEL_TRANSLATOR_SN74AVC1T45DBVR"))
    )
    (comp (ref "Y4")
      (value "ASH7KW-32.768kHz-L-T")
      (footprint "CRYSTAL_32.768KHZ_ASH7KW32768kHzLT")
      (description "OSC XO 32.768KHZ CMOS SMD")
      (fields (field (name "MANUFACTURER") "Abracon") (field (name "FREQUENCY") "32.768KHz"))
      (libsource (lib "Electronic Devices_LIB") (part "CRYSTAL_ABRACON_32.768KHZ"))
    )
    (comp (ref "Y5")
      (value "ECS-250-18-33-JTM-TR")
      (footprint "CRYSTAL_ECS-250-18-33-JTM-TR")
      (description "Crystal 25MHz ±20ppm (Tol) ±20ppm (Stability) 18pF FUND 40Ohm 4-Pin Mini-CSMD T/R")
      (fields (field (name "MANUFACTURER") "ECS International") (field (name "FREQUENCY") "25MHz"))
      (libsource (lib "Electronic Devices_LIB") (part "CRYSTAL_ECS_25MHZ_ECS-250-18-33-JTM-TR"))
    )
  )
  (nets
    (net (code "6") (name "/BT_DIS_B") (class "Default")
      (node (ref "J13") (pin "54") (pinfunction "W_DISABLE2_54") (pintype "passive"))
    )
    (net (code "7") (name "/BT_OSC_32KHZ") (class "Default")
      (node (ref "J13") (pin "50") (pinfunction "SUSCLK_50") (pintype "passive"))
      (node (ref "Y4") (pin "1") (pinfunction "OUTPUT_1") (pintype "passive"))
    )
    (net (code "8") (name "/BT_UART_WAKE_B") (class "Default")
      (node (ref "J13") (pin "20") (pinfunction "UART_WAKE_20") (pintype "passive"))
    )
    (net (code "9") (name "/I2C1_SCL") (class "Default")
      (node (ref "R149") (pin "1") (pinfunction "1_1") (pintype "passive"))
      (node (ref "U10") (pin "2") (pinfunction "A1_2") (pintype "passive"))
      (node (ref "U12") (pin "8") (pinfunction "SCLK_3.3_8") (pintype "passive"))
    )
    (net (code "10") (name "/I2C1_SDA") (class "Default")
      (node (ref "R148") (pin "1") (pinfunction "1_1") (pintype "passive"))
      (node (ref "U10") (pin "3") (pinfunction "A2_3") (pintype "passive"))
      (node (ref "U12") (pin "9") (pinfunction "SDATA_3.3_9") (pintype "passive"))
    )
    (net (code "11") (name "/I2C3_SCL") (class "Default")
      (node (ref "J13") (pin "60") (pinfunction "I2C_CLK_60") (pintype "passive"))
      (node (ref "U10") (pin "13") (pinfunction "B1_13") (pintype "passive"))
    )
    (net (code "12") (name "/I2C3_SDA") (class "Default")
      (node (ref "J13") (pin "58") (pinfunction "I2C_DATA_58") (pintype "passive"))
      (node (ref "U10") (pin "12") (pinfunction "B2_12") (pintype "passive"))
    )
    (net (code "13") (name "/LED1") (class "Default")
      (node (ref "D10") (pin "1") (pinfunction "C_1") (pintype "passive"))
      (node (ref "J13") (pin "6") (pinfunction "LED1_6") (pintype "passive"))
    )
    (net (code "14") (name "/LED2") (class "Default")
      (node (ref "D11") (pin "1") (pinfunction "C_1") (pintype "passive"))
      (node (ref "J13") (pin "16") (pinfunction "LED2_16") (pintype "passive"))
    )
    (net (code "15") (name "/M.2_PCIE0_RX_N") (class "Default")
      (node (ref "J13") (pin "43") (pinfunction "PER_N0_43") (pintype "passive"))
      (node (ref "R152") (pin "2") (pinfunction "2_2") (pintype "passive"))
    )
    (net (code "16") (name "/M.2_PCIE0_RX_P") (class "Default")
      (node (ref "J13") (pin "41") (pinfunction "PER_P0_41") (pintype "passive"))
      (node (ref "R151") (pin "2") (pinfunction "2_2") (pintype "passive"))
    )
    (net (code "17") (name "/M.2_PCIE0_TX_N") (class "Default")
      (node (ref "C283") (pin "1") (pinfunction "1_1") (pintype "passive"))
      (node (ref "J13") (pin "37") (pinfunction "PET_N0_37") (pintype "passive"))
    )
    (net (code "18") (name "/M.2_PCIE0_TX_P") (class "Default")
      (node (ref "C282") (pin "1") (pinfunction "1_1") (pintype "passive"))
      (node (ref "J13") (pin "35") (pinfunction "PET_P0_35") (pintype "passive"))
    )
    (net (code "19") (name "/M.2_SAI0_RXC") (class "Default")
      (node (ref "R139") (pin "2") (pinfunction "2_2") (pintype "passive"))
      (node (ref "TP45") (pin "1") (pinfunction "1_1") (pintype "passive"))
    )
    (net (code "20") (name "/M.2_SAI0_RXD") (class "Default")
      (node (ref "J13") (pin "12") (pinfunction "I2S_SD_IN_12") (pintype "passive"))
      (node (ref "R138") (pin "2") (pinfunction "2_2") (pintype "passive"))
    )
    (net (code "21") (name "/M.2_SAI0_TXC") (class "Default")
      (node (ref "J13") (pin "8") (pinfunction "I2S_SCK_8") (pintype "passive"))
      (node (ref "R140") (pin "2") (pinfunction "2_2") (pintype "passive"))
    )
    (net (code "22") (name "/M.2_SAI0_TXD") (class "Default")
      (node (ref "J13") (pin "14") (pinfunction "I2S_SD_OUT_14") (pintype "passive"))
      (node (ref "R141") (pin "2") (pinfunction "2_2") (pintype "passive"))
    )
    (net (code "23") (name "/M.2_SAI0_TXFS") (class "Default")
      (node (ref "J13") (pin "10") (pinfunction "I2S_WS_10") (pintype "passive"))
      (node (ref "R142") (pin "2") (pinfunction "2_2") (pintype "passive"))
    )
    (net (code "24") (name "/M.2_USB_DN") (class "Default")
      (node (ref "J13") (pin "5") (pinfunction "USB_D-_5") (pintype "passive+no_connect"))
    )
    (net (code "25") (name "/M.2_USB_DP") (class "Default")
      (node (ref "J13") (pin "3") (pinfunction "USB_D+_3") (pintype "passive+no_connect"))
    )
    (net (code "26") (name "/M.2_WIFI_EN") (class "Default")
      (node (ref "J13") (pin "23") (pinfunction "SDIO_RST_23") (pintype "passive"))
      (node (ref "R146") (pin "1") (pinfunction "1_1") (pintype "passive"))
      (node (ref "U10") (pin "5") (pinfunction "A4_5") (pintype "passive"))
    )
    (net (code "27") (name "/M.2_WIFI_WAKE_B") (class "Default")
      (node (ref "J13") (pin "21") (pinfunction "SDIO_WAKE_21") (pintype "passive"))
      (node (ref "R147") (pin "1") (pinfunction "1_1") (pintype "passive"))
      (node (ref "U10") (pin "4") (pinfunction "A3_4") (pintype "passive"))
    )
    (net (code "28") (name "/M2_CLKREQ_B") (class "Default")
      (node (ref "R155") (pin "1") (pinfunction "1_1") (pintype "passive"))
      (node (ref "R169") (pin "1") (pinfunction "1_1") (pintype "passive"))
      (node (ref "U15") (pin "2") (pinfunction "B_2") (pintype "passive"))
    )
    (net (code "29") (name "/MICRO_REFCLK_N") (class "Default")
      (node (ref "U11") (pin "6") (pinfunction "C0_N_6") (pintype "passive"))
      (node (ref "U13") (pin "6") (pinfunction "C0_N_6") (pintype "passive"))
    )
    (net (code "30") (name "/MICRO_REFCLK_P") (class "Default")
      (node (ref "U11") (pin "5") (pinfunction "C0_P_5") (pintype "passive"))
      (node (ref "U13") (pin "5") (pinfunction "C0_P_5") (pintype "passive"))
    )
    (net (code "31") (name "/PCIE0_REF_CLK_N") (class "Default")
      (node (ref "R137") (pin "2") (pinfunction "2_2") (pintype "passive"))
      (node (ref "U11") (pin "9") (pinfunction "A0_N_9") (pintype "passive"))
    )
    (net (code "32") (name "/PCIE0_REF_CLK_P") (class "Default")
      (node (ref "R136") (pin "2") (pinfunction "2_2") (pintype "passive"))
      (node (ref "U11") (pin "10") (pinfunction "A0_P_10") (pintype "passive"))
    )
    (net (code "33") (name "/PCIE0_RX_N") (class "Default")
      (node (ref "R152") (pin "1") (pinfunction "1_1") (pintype "passive"))
    )
    (net (code "34") (name "/PCIE0_RX_P") (class "Default")
      (node (ref "R151") (pin "1") (pinfunction "1_1") (pintype "passive"))
    )
    (net (code "35") (name "/PCIE0_TX_N") (class "Default")
      (node (ref "C283") (pin "2") (pinfunction "2_2") (pintype "passive"))
    )
    (net (code "36") (name "/PCIE0_TX_P") (class "Default")
      (node (ref "C282") (pin "2") (pinfunction "2_2") (pintype "passive"))
    )
    (net (code "37") (name "/PCIE_CLK_SEL") (class "Default")
      (node (ref "R154") (pin "2") (pinfunction "2_2") (pintype "passive"))
      (node (ref "U11") (pin "12") (pinfunction "SEL_12") (pintype "passive"))
      (node (ref "U13") (pin "12") (pinfunction "SEL_12") (pintype "passive"))
    )
    (net (code "38") (name "/PCIE_CONN_REFCLK_N") (class "Default")
      (node (ref "J13") (pin "49") (pinfunction "REFCLK_N0_49") (pintype "passive"))
      (node (ref "R157") (pin "2") (pinfunction "2_2") (pintype "passive"))
      (node (ref "U13") (pin "9") (pinfunction "A0_N_9") (pintype "passive"))
    )
    (net (code "39") (name "/PCIE_CONN_REFCLK_P") (class "Default")
      (node (ref "J13") (pin "47") (pinfunction "REFCLK_P0_47") (pintype "passive"))
      (node (ref "R156") (pin "2") (pinfunction "2_2") (pintype "passive"))
      (node (ref "U13") (pin "10") (pinfunction "A0_P_10") (pintype "passive"))
    )
    (net (code "40") (name "/PCIE_CTRL_CLKREQ_B") (class "Default")
      (node (ref "R168") (pin "1") (pinfunction "1_1") (pintype "passive"))
      (node (ref "U15") (pin "1") (pinfunction "A_1") (pintype "passive"))
    )
    (net (code "41") (name "/PCIE_CTRL_PERST_B") (class "Default")
      (node (ref "R153") (pin "1") (pinfunction "1_1") (pintype "passive"))
    )
    (net (code "42") (name "/PCIE_CTRL_WAKE_B") (class "Default")
      (node (ref "J13") (pin "55") (pinfunction "PEWAKE0_55") (pintype "passive"))
      (node (ref "R150") (pin "1") (pinfunction "1_1") (pintype "passive"))
    )
    (net (code "43") (name "/PCI_CLKREQ") (class "Default")
      (node (ref "R163") (pin "2") (pinfunction "2_2") (pintype "passive"))
      (node (ref "R166") (pin "1") (pinfunction "1_1") (pintype "passive"))
      (node (ref "R167") (pin "1") (pinfunction "1_1") (pintype "passive"))
      (node (ref "R167") (pin "2") (pinfunction "2_2") (pintype "passive"))
      (node (ref "U12") (pin "22") (pinfunction "CKPWRGD_PD#_22") (pintype "passive"))
      (node (ref "U15") (pin "4") (pinfunction "Y_4") (pintype "passive"))
    )
    (net (code "44") (name "/PCI_XTAL_X1") (class "Default")
      (node (ref "C294") (pin "2") (pinfunction "2_2") (pintype "passive"))
      (node (ref "U12") (pin "1") (pinfunction "X1_25_1") (pintype "passive"))
      (node (ref "Y5") (pin "1") (pinfunction "IN_1") (pintype "passive"))
    )
    (net (code "45") (name "/PCI_XTAL_X2") (class "Default")
      (node (ref "R160") (pin "2") (pinfunction "2_2") (pintype "passive"))
      (node (ref "U12") (pin "2") (pinfunction "X2_2") (pintype "passive"))
    )
    (net (code "46") (name "/REFCLK1_N") (class "Default")
      (node (ref "R159") (pin "2") (pinfunction "2_2") (pintype "passive"))
      (node (ref "U11") (pin "7") (pinfunction "B0_N_7") (pintype "passive"))
    )
    (net (code "47") (name "/REFCLK1_P") (class "Default")
      (node (ref "R158") (pin "2") (pinfunction "2_2") (pintype "passive"))
      (node (ref "U11") (pin "8") (pinfunction "B0_P_8") (pintype "passive"))
    )
    (net (code "48") (name "/REFCLK2_N") (class "Default")
      (node (ref "R162") (pin "2") (pinfunction "2_2") (pintype "passive"))
      (node (ref "U13") (pin "7") (pinfunction "B0_N_7") (pintype "passive"))
    )
    (net (code "49") (name "/REFCLK2_P") (class "Default")
      (node (ref "R161") (pin "2") (pinfunction "2_2") (pintype "passive"))
      (node (ref "U13") (pin "8") (pinfunction "B0_P_8") (pintype "passive"))
    )
    (net (code "50") (name "/SS_CNTRL") (class "Default")
      (node (ref "U14") (pin "2") (pinfunction "A_2") (pintype "passive"))
    )
    (net (code "51") (name "/SS_CNTRL_B") (class "Default")
      (node (ref "U14") (pin "4") (pinfunction "Y_4") (pintype "passive"))
      (node (ref "U16") (pin "4") (pinfunction "B_4") (pintype "passive"))
    )
    (net (code "52") (name "/SS_EN_TRI") (class "Default")
      (node (ref "U12") (pin "23") (pinfunction "SS_EN_TRI_23") (pintype "passive"))
      (node (ref "U16") (pin "3") (pinfunction "A_3") (pintype "passive"))
    )
    (net (code "53") (name "/UART1_CTS_B") (class "Default")
      (node (ref "J13") (pin "34") (pinfunction "UART_CTS_34") (pintype "passive"))
    )
    (net (code "54") (name "/UART1_RTS_B") (class "Default")
      (node (ref "J13") (pin "36") (pinfunction "UART_RTS_36") (pintype "passive"))
    )
    (net (code "55") (name "/UART1_RX") (class "Default")
      (node (ref "J13") (pin "22") (pinfunction "UART_RXD_22") (pintype "passive"))
    )
    (net (code "56") (name "/UART1_TX") (class "Default")
      (node (ref "J13") (pin "32") (pinfunction "UART_TXD_32") (pintype "passive"))
    )
    (net (code "57") (name "/WIFI_DIS_B") (class "Default")
      (node (ref "J13") (pin "56") (pinfunction "W_DISABLE1_56") (pintype "passive"))
    )
    (net (code "58") (name "/WIFI_EN") (class "Default")
      (node (ref "U10") (pin "10") (pinfunction "B4_10") (pintype "passive"))
    )
    (net (code "59") (name "/WIFI_WAKE_B") (class "Default")
      (node (ref "U10") (pin "11") (pinfunction "B3_11") (pintype "passive"))
    )
    (net (code "60") (name "/XTAL2") (class "Default")
      (node (ref "C295") (pin "2") (pinfunction "2_2") (pintype "passive"))
      (node (ref "R160") (pin "1") (pinfunction "1_1") (pintype "passive"))
      (node (ref "Y5") (pin "3") (pinfunction "OUT_3") (pintype "passive"))
    )
    (net (code "66") (name "1V8") (class "Default")
      (node (ref "C280") (pin "2") (pinfunction "2_2") (pintype "passive"))
      (node (ref "C284") (pin "2") (pinfunction "2_2") (pintype "passive"))
      (node (ref "C285") (pin "2") (pinfunction "2_2") (pintype "passive"))
      (node (ref "C298") (pin "1") (pinfunction "1_1") (pintype "passive"))
      (node (ref "FB4") (pin "2") (pinfunction "2_2") (pintype "passive"))
      (node (ref "FB5") (pin "1") (pinfunction "1_1") (pintype "passive"))
      (node (ref "R145") (pin "2") (pinfunction "2_2") (pintype "passive"))
      (node (ref "R146") (pin "2") (pinfunction "2_2") (pintype "passive"))
      (node (ref "R147") (pin "2") (pinfunction "2_2") (pintype "passive"))
      (node (ref "R148") (pin "2") (pinfunction "2_2") (pintype "passive"))
      (node (ref "R149") (pin "2") (pinfunction "2_2") (pintype "passive"))
      (node (ref "R166") (pin "2") (pinfunction "2_2") (pintype "passive"))
      (node (ref "U10") (pin "1") (pinfunction "VCCA_1") (pintype "power_in"))
      (node (ref "U12") (pin "7") (pinfunction "VDDDIG1.8_7") (pintype "passive"))
      (node (ref "U16") (pin "1") (pinfunction "VCCA_1") (pintype "passive"))
    )
    (net (code "67") (name "3V3") (class "Default")
      (node (ref "C275") (pin "2") (pinfunction "2_2") (pintype "passive"))
      (node (ref "C276") (pin "2") (pinfunction "2_2") (pintype "passive"))
      (node (ref "C277") (pin "2") (pinfunction "2_2") (pintype "passive"))
      (node (ref "C278") (pin "2") (pinfunction "2_2") (pintype "passive"))
      (node (ref "C279") (pin "2") (pinfunction "2_2") (pintype "passive"))
      (node (ref "C281") (pin "2") (pinfunction "2_2") (pintype "passive"))
      (node (ref "C292") (pin "2") (pinfunction "2_2") (pintype "passive"))
      (node (ref "C293") (pin "2") (pinfunction "2_2") (pintype "passive"))
      (node (ref "C296") (pin "1") (pinfunction "1_1") (pintype "passive"))
      (node (ref "C297") (pin "1") (pinfunction "1_1") (pintype "passive"))
      (node (ref "C299") (pin "1") (pinfunction "1_1") (pintype "passive"))
      (node (ref "J13") (pin "2") (pinfunction "3V3_1_2") (pintype "passive"))
      (node (ref "J13") (pin "4") (pinfunction "3V3_2_4") (pintype "passive"))
      (node (ref "J13") (pin "72") (pinfunction "3V3_3_72") (pintype "passive"))
      (node (ref "J13") (pin "74") (pinfunction "3V3_4_74") (pintype "passive"))
      (node (ref "R143") (pin "2") (pinfunction "2_2") (pintype "passive"))
      (node (ref "R144") (pin "2") (pinfunction "2_2") (pintype "passive"))
      (node (ref "R150") (pin "2") (pinfunction "2_2") (pintype "passive"))
      (node (ref "R154") (pin "1") (pinfunction "1_1") (pintype "passive"))
      (node (ref "R168") (pin "2") (pinfunction "2_2") (pintype "passive"))
      (node (ref "R169") (pin "2") (pinfunction "2_2") (pintype "passive"))
      (node (ref "U10") (pin "14") (pinfunction "VCCB_14") (pintype "power_in"))
      (node (ref "U11") (pin "4") (pinfunction "VDD_4") (pintype "power_in"))
      (node (ref "U13") (pin "4") (pinfunction "VDD_4") (pintype "power_in"))
      (node (ref "U14") (pin "5") (pinfunction "VCC_5") (pintype "power_in"))
      (node (ref "U15") (pin "5") (pinfunction "VCC_5") (pintype "passive"))
      (node (ref "U16") (pin "6") (pinfunction "VCCB_6") (pintype "passive"))
      (node (ref "Y4") (pin "3") (pinfunction "OE_3") (pintype "passive"))
      (node (ref "Y4") (pin "4") (pinfunction "VDD_4") (pintype "passive"))
    )
    (net (code "68") (name "GND") (class "Default")
      (node (ref "C275") (pin "1") (pinfunction "1_1") (pintype "passive"))
      (node (ref "C276") (pin "1") (pinfunction "1_1") (pintype "passive"))
      (node (ref "C277") (pin "1") (pinfunction "1_1") (pintype "passive"))
      (node (ref "C278") (pin "1") (pinfunction "1_1") (pintype "passive"))
      (node (ref "C279") (pin "1") (pinfunction "1_1") (pintype "passive"))
      (node (ref "C280") (pin "1") (pinfunction "1_1") (pintype "passive"))
      (node (ref "C281") (pin "1") (pinfunction "1_1") (pintype "passive"))
      (node (ref "C284") (pin "1") (pinfunction "1_1") (pintype "passive"))
      (node (ref "C285") (pin "1") (pinfunction "1_1") (pintype "passive"))
      (node (ref "C286") (pin "1") (pinfunction "1_1") (pintype "passive"))
      (node (ref "C287") (pin "1") (pinfunction "1_1") (pintype "passive"))
      (node (ref "C288") (pin "1") (pinfunction "1_1") (pintype "passive"))
      (node (ref "C289") (pin "1") (pinfunction "1_1") (pintype "passive"))
      (node (ref "C290") (pin "1") (pinfunction "1_1") (pintype "passive"))
      (node (ref "C291") (pin "1") (pinfunction "1_1") (pintype "passive"))
      (node (ref "C292") (pin "1") (pinfunction "1_1") (pintype "passive"))
      (node (ref "C293") (pin "1") (pinfunction "1_1") (pintype "passive"))
      (node (ref "C294") (pin "1") (pinfunction "1_1") (pintype "passive"))
      (node (ref "C295") (pin "1") (pinfunction "1_1") (pintype "passive"))
      (node (ref "C296") (pin "2") (pinfunction "2_2") (pintype "passive"))
      (node (ref "C297") (pin "2") (pinfunction "2_2") (pintype "passive"))
      (node (ref "C298") (pin "2") (pinfunction "2_2") (pintype "passive"))
      (node (ref "C299") (pin "2") (pinfunction "2_2") (pintype "passive"))
      (node (ref "J13") (pin "1") (pinfunction "GND1_1") (pintype "passive"))
      (node (ref "J13") (pin "18") (pinfunction "GND3_18") (pintype "passive"))
      (node (ref "J13") (pin "33") (pinfunction "GND5_33") (pintype "passive"))
      (node (ref "J13") (pin "39") (pinfunction "GND4_39") (pintype "passive"))
      (node (ref "J13") (pin "45") (pinfunction "GND6_45") (pintype "passive"))
      (node (ref "J13") (pin "51") (pinfunction "GND7_51") (pintype "passive"))
      (node (ref "J13") (pin "57") (pinfunction "GND8_57") (pintype "passive"))
      (node (ref "J13") (pin "63") (pinfunction "GND9_63") (pintype "passive"))
      (node (ref "J13") (pin "69") (pinfunction "GND10_69") (pintype "passive"))
      (node (ref "J13") (pin "7") (pinfunction "GND2_7") (pintype "passive"))
      (node (ref "J13") (pin "75") (pinfunction "GND11_75") (pintype "passive"))
      (node (ref "J13") (pin "S1") (pinfunction "SHIELD_S1") (pintype "passive"))
      (node (ref "J13") (pin "S2") (pinfunction "SHIELD_S2") (pintype "passive"))
      (node (ref "R156") (pin "1") (pinfunction "1_1") (pintype "passive"))
      (node (ref "R157") (pin "1") (pinfunction "1_1") (pintype "passive"))
      (node (ref "R163") (pin "1") (pinfunction "1_1") (pintype "passive"))
      (node (ref "R164") (pin "1") (pinfunction "1_1") (pintype "passive"))
      (node (ref "R165") (pin "1") (pinfunction "1_1") (pintype "passive"))
      (node (ref "R170") (pin "2") (pinfunction "2_2") (pintype "passive"))
      (node (ref "U10") (pin "6") (pinfunction "NC_6") (pintype "passive"))
      (node (ref "U10") (pin "9") (pinfunction "NC_9") (pintype "passive"))
      (node (ref "U11") (pin "11") (pinfunction "VSS_11") (pintype "power_in"))
      (node (ref "U11") (pin "13") (pinfunction "A1_P_13") (pintype "passive"))
      (node (ref "U11") (pin "14") (pinfunction "A1_N_14") (pintype "passive"))
      (node (ref "U11") (pin "17") (pinfunction "EPAD_17") (pintype "power_in"))
      (node (ref "U11") (pin "3") (pinfunction "XSD_3") (pintype "passive"))
      (node (ref "U12") (pin "10") (pinfunction "GND_1_10") (pintype "passive"))
      (node (ref "U12") (pin "15") (pinfunction "GNDA_15") (pintype "passive"))
      (node (ref "U12") (pin "21") (pinfunction "GND_2_21") (pintype "passive"))
      (node (ref "U12") (pin "24") (pinfunction "GNDXTAL_24") (pintype "passive"))
      (node (ref "U12") (pin "25") (pinfunction "GND_3_25") (pintype "passive"))
      (node (ref "U12") (pin "5") (pinfunction "GNDREF_5") (pintype "passive"))
      (node (ref "U12") (pin "6") (pinfunction "GNDDIG_6") (pintype "passive"))
      (node (ref "U13") (pin "11") (pinfunction "VSS_11") (pintype "power_in"))
      (node (ref "U13") (pin "13") (pinfunction "A1_P_13") (pintype "passive"))
      (node (ref "U13") (pin "14") (pinfunction "A1_N_14") (pintype "passive"))
      (node (ref "U13") (pin "17") (pinfunction "EPAD_17") (pintype "power_in"))
      (node (ref "U13") (pin "3") (pinfunction "XSD_3") (pintype "passive"))
      (node (ref "U14") (pin "1") (pinfunction "NC_1") (pintype "passive"))
      (node (ref "U14") (pin "3") (pinfunction "GND_3") (pintype "power_in"))
      (node (ref "U15") (pin "3") (pinfunction "GND_3") (pintype "passive"))
      (node (ref "U16") (pin "2") (pinfunction "GND_2") (pintype "passive"))
      (node (ref "Y4") (pin "2") (pinfunction "GND_2") (pintype "passive"))
      (node (ref "Y5") (pin "2") (pinfunction "2_2") (pintype "passive"))
      (node (ref "Y5") (pin "4") (pinfunction "4_4") (pintype "passive"))
    )
    (net (code "69") (name "Net-(D10-A)") (class "Default")
      (node (ref "D10") (pin "2") (pinfunction "A_2") (pintype "passive"))
      (node (ref "R143") (pin "1") (pinfunction "1_1") (pintype "passive"))
    )
    (net (code "70") (name "Net-(D11-A)") (class "Default")
      (node (ref "D11") (pin "2") (pinfunction "A_2") (pintype "passive"))
      (node (ref "R144") (pin "1") (pinfunction "1_1") (pintype "passive"))
    )
    (net (code "71") (name "Net-(J13-CLKREQ0)") (class "Default")
      (node (ref "J13") (pin "53") (pinfunction "CLKREQ0_53") (pintype "passive"))
      (node (ref "R155") (pin "2") (pinfunction "2_2") (pintype "passive"))
    )
    (net (code "72") (name "Net-(J13-PERST0)") (class "Default")
      (node (ref "J13") (pin "52") (pinfunction "PERST0_52") (pintype "passive"))
      (node (ref "R153") (pin "2") (pinfunction "2_2") (pintype "passive"))
    )
    (net (code "73") (name "Net-(U10-OE)") (class "Default")
      (node (ref "R145") (pin "1") (pinfunction "1_1") (pintype "passive"))
      (node (ref "U10") (pin "8") (pinfunction "OE_8") (pintype "passive"))
    )
    (net (code "74") (name "Net-(U12-DIF0#)") (class "Default")
      (node (ref "R162") (pin "1") (pinfunction "1_1") (pintype "passive"))
      (node (ref "U12") (pin "14") (pinfunction "DIF0#_14") (pintype "passive"))
    )
    (net (code "75") (name "Net-(U12-DIF0)") (class "Default")
      (node (ref "R161") (pin "1") (pinfunction "1_1") (pintype "passive"))
      (node (ref "U12") (pin "13") (pinfunction "DIF0_13") (pintype "passive"))
    )
    (net (code "76") (name "Net-(U12-DIF1#)") (class "Default")
      (node (ref "R159") (pin "1") (pinfunction "1_1") (pintype "passive"))
      (node (ref "U12") (pin "18") (pinfunction "DIF1#_18") (pintype "passive"))
    )
    (net (code "77") (name "Net-(U12-DIF1)") (class "Default")
      (node (ref "R158") (pin "1") (pinfunction "1_1") (pintype "passive"))
      (node (ref "U12") (pin "17") (pinfunction "DIF1_17") (pintype "passive"))
    )
    (net (code "78") (name "Net-(U12-OE0#)") (class "Default")
      (node (ref "R164") (pin "2") (pinfunction "2_2") (pintype "passive"))
      (node (ref "U12") (pin "12") (pinfunction "OE0#_12") (pintype "passive"))
    )
    (net (code "79") (name "Net-(U12-OE1#)") (class "Default")
      (node (ref "R165") (pin "2") (pinfunction "2_2") (pintype "passive"))
      (node (ref "U12") (pin "19") (pinfunction "OE1#_19") (pintype "passive"))
    )
    (net (code "80") (name "Net-(U12-SADR{slash}REF1.8)") (class "Default")
      (node (ref "TP46") (pin "1") (pinfunction "1_1") (pintype "passive"))
      (node (ref "U12") (pin "4") (pinfunction "SADR/REF1.8_4") (pintype "passive"))
    )
    (net (code "81") (name "Net-(U12-VDD1.8_1)") (class "Default")
      (node (ref "C289") (pin "2") (pinfunction "2_2") (pintype "passive"))
      (node (ref "C290") (pin "2") (pinfunction "2_2") (pintype "passive"))
      (node (ref "C291") (pin "2") (pinfunction "2_2") (pintype "passive"))
      (node (ref "FB5") (pin "2") (pinfunction "2_2") (pintype "passive"))
      (node (ref "U12") (pin "11") (pinfunction "VDD1.8_1_11") (pintype "passive"))
      (node (ref "U12") (pin "20") (pinfunction "VDD1.8_2_20") (pintype "passive"))
    )
    (net (code "82") (name "Net-(U12-VDDA1.8)") (class "Default")
      (node (ref "C286") (pin "2") (pinfunction "2_2") (pintype "passive"))
      (node (ref "C287") (pin "2") (pinfunction "2_2") (pintype "passive"))
      (node (ref "C288") (pin "2") (pinfunction "2_2") (pintype "passive"))
      (node (ref "FB4") (pin "1") (pinfunction "1_1") (pintype "passive"))
      (node (ref "U12") (pin "16") (pinfunction "VDDA1.8_16") (pintype "passive"))
      (node (ref "U12") (pin "3") (pinfunction "VDDXTAL1.8_3") (pintype "passive"))
    )
    (net (code "83") (name "Net-(U16-DIR)") (class "Default")
      (node (ref "R170") (pin "1") (pinfunction "1_1") (pintype "passive"))
      (node (ref "U16") (pin "5") (pinfunction "DIR_5") (pintype "passive"))
    )
    (net (code "84") (name "unconnected-(J13-ALERT-Pad62)") (class "Default")
      (node (ref "J13") (pin "62") (pinfunction "ALERT_62") (pintype "passive+no_connect"))
    )
    (net (code "85") (name "unconnected-(J13-CLKREQ1-Pad68)") (class "Default")
      (node (ref "J13") (pin "68") (pinfunction "CLKREQ1_68") (pintype "passive+no_connect"))
    )
    (net (code "86") (name "unconnected-(J13-COEX1-Pad48)") (class "Default")
      (node (ref "J13") (pin "48") (pinfunction "COEX1_48") (pintype "passive+no_connect"))
    )
    (net (code "87") (name "unconnected-(J13-COEX2-Pad46)") (class "Default")
      (node (ref "J13") (pin "46") (pinfunction "COEX2_46") (pintype "passive+no_connect"))
    )
    (net (code "88") (name "unconnected-(J13-COEX3-Pad44)") (class "Default")
      (node (ref "J13") (pin "44") (pinfunction "COEX3_44") (pintype "passive+no_connect"))
    )
    (net (code "89") (name "unconnected-(J13-PERST1-Pad66)") (class "Default")
      (node (ref "J13") (pin "66") (pinfunction "PERST1_66") (pintype "passive+no_connect"))
    )
    (net (code "90") (name "unconnected-(J13-PER_N1-Pad67)") (class "Default")
      (node (ref "J13") (pin "67") (pinfunction "PER_N1_67") (pintype "passive+no_connect"))
    )
    (net (code "91") (name "unconnected-(J13-PER_P1-Pad65)") (class "Default")
      (node (ref "J13") (pin "65") (pinfunction "PER_P1_65") (pintype "passive+no_connect"))
    )
    (net (code "92") (name "unconnected-(J13-PET_N1-Pad61)") (class "Default")
      (node (ref "J13") (pin "61") (pinfunction "PET_N1_61") (pintype "passive+no_connect"))
    )
    (net (code "93") (name "unconnected-(J13-PET_P1-Pad59)") (class "Default")
      (node (ref "J13") (pin "59") (pinfunction "PET_P1_59") (pintype "passive+no_connect"))
    )
    (net (code "94") (name "unconnected-(J13-PEWAKE1-Pad70)") (class "Default")
      (node (ref "J13") (pin "70") (pinfunction "PEWAKE1_70") (pintype "passive+no_connect"))
    )
    (net (code "95") (name "unconnected-(J13-REFCLK_N1-Pad73)") (class "Default")
      (node (ref "J13") (pin "73") (pinfunction "REFCLK_N1_73") (pintype "passive+no_connect"))
    )
    (net (code "96") (name "unconnected-(J13-REFCLK_P1-Pad71)") (class "Default")
      (node (ref "J13") (pin "71") (pinfunction "REFCLK_P1_71") (pintype "passive+no_connect"))
    )
    (net (code "97") (name "unconnected-(J13-RESERVED-Pad64)") (class "Default")
      (node (ref "J13") (pin "64") (pinfunction "RESERVED_64") (pintype "passive+no_connect"))
    )
    (net (code "98") (name "unconnected-(J13-SDIO_CLK-Pad9)") (class "Default")
      (node (ref "J13") (pin "9") (pinfunction "SDIO_CLK_9") (pintype "passive+no_connect"))
    )
    (net (code "99") (name "unconnected-(J13-SDIO_CMD-Pad11)") (class "Default")
      (node (ref "J13") (pin "11") (pinfunction "SDIO_CMD_11") (pintype "passive+no_connect"))
    )
    (net (code "100") (name "unconnected-(J13-SDIO_DATA0-Pad13)") (class "Default")
      (node (ref "J13") (pin "13") (pinfunction "SDIO_DATA0_13") (pintype "passive+no_connect"))
    )
    (net (code "101") (name "unconnected-(J13-SDIO_DATA1-Pad15)") (class "Default")
      (node (ref "J13") (pin "15") (pinfunction "SDIO_DATA1_15") (pintype "passive+no_connect"))
    )
    (net (code "102") (name "unconnected-(J13-SDIO_DATA2-Pad17)") (class "Default")
      (node (ref "J13") (pin "17") (pinfunction "SDIO_DATA2_17") (pintype "passive+no_connect"))
    )
    (net (code "103") (name "unconnected-(J13-SDIO_DATA3-Pad19)") (class "Default")
      (node (ref "J13") (pin "19") (pinfunction "SDIO_DATA3_19") (pintype "passive+no_connect"))
    )
    (net (code "104") (name "unconnected-(J13-VEN_DEF1-Pad38)") (class "Default")
      (node (ref "J13") (pin "38") (pinfunction "VEN_DEF1_38") (pintype "passive+no_connect"))
    )
    (net (code "105") (name "unconnected-(J13-VEN_DEF2-Pad40)") (class "Default")
      (node (ref "J13") (pin "40") (pinfunction "VEN_DEF2_40") (pintype "passive+no_connect"))
    )
    (net (code "106") (name "unconnected-(J13-VEN_DEF3-Pad42)") (class "Default")
      (node (ref "J13") (pin "42") (pinfunction "VEN_DEF3_42") (pintype "passive+no_connect"))
    )
    (net (code "107") (name "unconnected-(R136-Pad1)") (class "Default")
      (node (ref "R136") (pin "1") (pinfunction "1_1") (pintype "passive"))
    )
    (net (code "108") (name "unconnected-(R137-Pad1)") (class "Default")
      (node (ref "R137") (pin "1") (pinfunction "1_1") (pintype "passive"))
    )
    (net (code "109") (name "unconnected-(R138-Pad1)") (class "Default")
      (node (ref "R138") (pin "1") (pinfunction "1_1") (pintype "passive"))
    )
    (net (code "110") (name "unconnected-(R139-Pad1)") (class "Default")
      (node (ref "R139") (pin "1") (pinfunction "1_1") (pintype "passive"))
    )
    (net (code "111") (name "unconnected-(R140-Pad1)") (class "Default")
      (node (ref "R140") (pin "1") (pinfunction "1_1") (pintype "passive"))
    )
    (net (code "112") (name "unconnected-(R141-Pad1)") (class "Default")
      (node (ref "R141") (pin "1") (pinfunction "1_1") (pintype "passive"))
    )
    (net (code "113") (name "unconnected-(R142-Pad1)") (class "Default")
      (node (ref "R142") (pin "1") (pinfunction "1_1") (pintype "passive"))
    )
    (net (code "114") (name "unconnected-(U10-EP-Pad15)") (class "Default")
      (node (ref "U10") (pin "15") (pinfunction "EP_15") (pintype "passive+no_connect"))
    )
    (net (code "115") (name "unconnected-(U10-GND-Pad7)") (class "Default")
      (node (ref "U10") (pin "7") (pinfunction "GND_7") (pintype "power_in+no_connect"))
    )
    (net (code "116") (name "unconnected-(U11-B1_N-Pad1)") (class "Default")
      (node (ref "U11") (pin "1") (pinfunction "B1_N_1") (pintype "passive+no_connect"))
    )
    (net (code "117") (name "unconnected-(U11-B1_P-Pad2)") (class "Default")
      (node (ref "U11") (pin "2") (pinfunction "B1_P_2") (pintype "passive+no_connect"))
    )
    (net (code "118") (name "unconnected-(U11-C1_N-Pad16)") (class "Default")
      (node (ref "U11") (pin "16") (pinfunction "C1_N_16") (pintype "passive+no_connect"))
    )
    (net (code "119") (name "unconnected-(U11-C1_P-Pad15)") (class "Default")
      (node (ref "U11") (pin "15") (pinfunction "C1_P_15") (pintype "passive+no_connect"))
    )
    (net (code "120") (name "unconnected-(U13-B1_N-Pad1)") (class "Default")
      (node (ref "U13") (pin "1") (pinfunction "B1_N_1") (pintype "passive+no_connect"))
    )
    (net (code "121") (name "unconnected-(U13-B1_P-Pad2)") (class "Default")
      (node (ref "U13") (pin "2") (pinfunction "B1_P_2") (pintype "passive+no_connect"))
    )
    (net (code "122") (name "unconnected-(U13-C1_N-Pad16)") (class "Default")
      (node (ref "U13") (pin "16") (pinfunction "C1_N_16") (pintype "passive+no_connect"))
    )
    (net (code "123") (name "unconnected-(U13-C1_P-Pad15)") (class "Default")
      (node (ref "U13") (pin "15") (pinfunction "C1_P_15") (pintype "passive+no_connect"))
    )
  )
)
